# source.net
KiCad netlist of a schematic drawn in Altium Designer
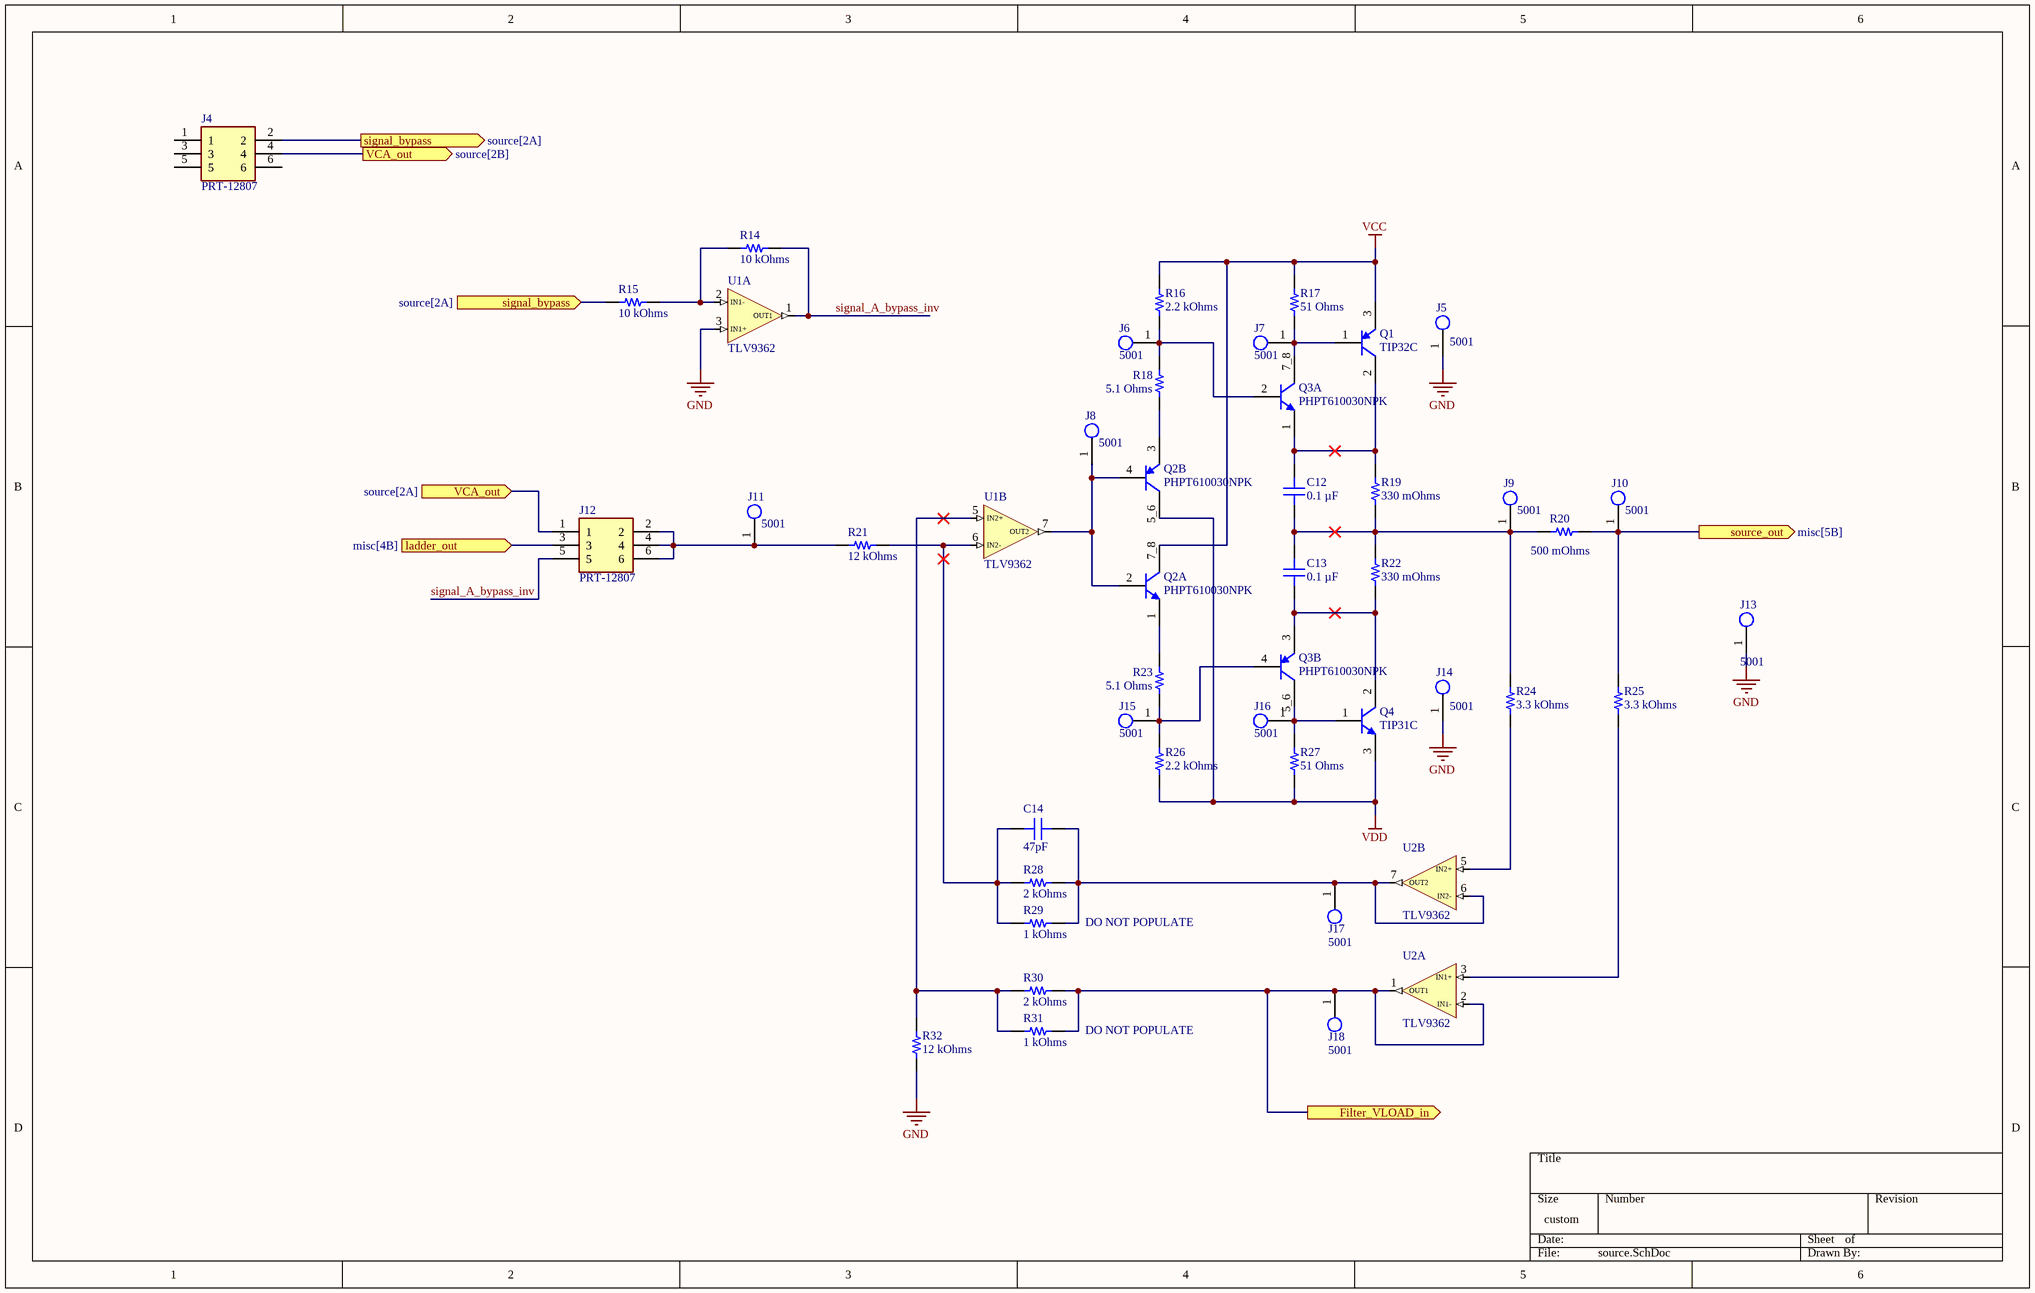
[diagram p0: source.SchDoc]

(export (version "E")
  (design (tool "Eeschema 10.0.6"))
  (components
    (comp (ref "C12")
      (value "0.1 µF")
      (footprint "CAP 1206_3216 - 0.8MM")
      (description "CAP CER 0.1UF 50V X7R 1206")
      (fields
        (field (name "PART NUMBER") "885012208087")
        (field (name "CAPACITANCE") "0.1 µF")
        (field (name "MANUFACTURER") "Würth Elektronik")
      )
      (libsource (lib "Celestial Altium Library - altium_library") (part "Capacitor"))
    )
    (comp (ref "C13")
      (value "0.1 µF")
      (footprint "CAP 1206_3216 - 0.8MM")
      (description "CAP CER 0.1UF 50V X7R 1206")
      (fields
        (field (name "PART NUMBER") "885012208087")
        (field (name "CAPACITANCE") "0.1 µF")
        (field (name "MANUFACTURER") "Würth Elektronik")
      )
      (libsource (lib "Celestial Altium Library - altium_library") (part "Capacitor"))
    )
    (comp (ref "C14")
      (value "47pF")
      (footprint "CAP 1206_3216 - 1.8MM")
      (description "CAP CER 47PF 1KV C0G/NP0 1206")
      (fields
        (field (name "PART NUMBER") "1206AA470KAT1A")
        (field (name "CAPACITANCE") "47pF")
        (field (name "MANUFACTURER") "AVX Corporation")
      )
      (libsource (lib "Celestial Altium Library - altium_library") (part "Capacitor"))
    )
    (comp (ref "J4")
      (value "PRT-12807")
      (footprint "HDRV6W82P254_2X3_762X500X884P")
      (description "Connector")
      (fields (field (name "MOUSER PART NUMBER") "474-PRT-12807"))
      (libsource (lib "za_koncar") (part "PRT-12807"))
    )
    (comp (ref "J5")
      (value "5001")
      (footprint "FP-5001-MFG")
      (description "PC TEST POINT MINIATURE BLACK")
      (libsource (lib "za_koncar") (part "CMP-2000-05181-2"))
    )
    (comp (ref "J6")
      (value "5001")
      (footprint "FP-5001-MFG")
      (description "PC TEST POINT MINIATURE BLACK")
      (libsource (lib "za_koncar") (part "CMP-2000-05181-2"))
    )
    (comp (ref "J7")
      (value "5001")
      (footprint "FP-5001-MFG")
      (description "PC TEST POINT MINIATURE BLACK")
      (libsource (lib "za_koncar") (part "CMP-2000-05181-2"))
    )
    (comp (ref "J8")
      (value "5001")
      (footprint "FP-5001-MFG")
      (description "PC TEST POINT MINIATURE BLACK")
      (libsource (lib "za_koncar") (part "CMP-2000-05181-2"))
    )
    (comp (ref "J9")
      (value "5001")
      (footprint "FP-5001-MFG")
      (description "PC TEST POINT MINIATURE BLACK")
      (libsource (lib "za_koncar") (part "CMP-2000-05181-2"))
    )
    (comp (ref "J10")
      (value "5001")
      (footprint "FP-5001-MFG")
      (description "PC TEST POINT MINIATURE BLACK")
      (libsource (lib "za_koncar") (part "CMP-2000-05181-2"))
    )
    (comp (ref "J11")
      (value "5001")
      (footprint "FP-5001-MFG")
      (description "PC TEST POINT MINIATURE BLACK")
      (libsource (lib "za_koncar") (part "CMP-2000-05181-2"))
    )
    (comp (ref "J12")
      (value "PRT-12807")
      (footprint "HDRV6W82P254_2X3_762X500X884P")
      (description "Connector")
      (fields (field (name "MOUSER PART NUMBER") "474-PRT-12807"))
      (libsource (lib "za_koncar") (part "PRT-12807"))
    )
    (comp (ref "J13")
      (value "5001")
      (footprint "FP-5001-MFG")
      (description "PC TEST POINT MINIATURE BLACK")
      (libsource (lib "za_koncar") (part "CMP-2000-05181-2"))
    )
    (comp (ref "J14")
      (value "5001")
      (footprint "FP-5001-MFG")
      (description "PC TEST POINT MINIATURE BLACK")
      (libsource (lib "za_koncar") (part "CMP-2000-05181-2"))
    )
    (comp (ref "J15")
      (value "5001")
      (footprint "FP-5001-MFG")
      (description "PC TEST POINT MINIATURE BLACK")
      (libsource (lib "za_koncar") (part "CMP-2000-05181-2"))
    )
    (comp (ref "J16")
      (value "5001")
      (footprint "FP-5001-MFG")
      (description "PC TEST POINT MINIATURE BLACK")
      (libsource (lib "za_koncar") (part "CMP-2000-05181-2"))
    )
    (comp (ref "J17")
      (value "5001")
      (footprint "FP-5001-MFG")
      (description "PC TEST POINT MINIATURE BLACK")
      (libsource (lib "za_koncar") (part "CMP-2000-05181-2"))
    )
    (comp (ref "J18")
      (value "5001")
      (footprint "FP-5001-MFG")
      (description "PC TEST POINT MINIATURE BLACK")
      (libsource (lib "za_koncar") (part "CMP-2000-05181-2"))
    )
    (comp (ref "Q1")
      (value "TIP32C")
      (footprint "ONSC-TO-220-3-221A-09")
      (description "Complementary Silicon Plastic Power Transistor, 3-Pin TO-220, Tube")
      (fields (field (name "MANUFACTURER") "On Semiconductor"))
      (libsource (lib "ON Semi General Purpose Transistors") (part "TIP32C"))
    )
    (comp (ref "Q2")
      (value "PHPT610030NPK")
      (footprint "TRANS_BUK9K18-40E,115")
      (libsource (lib "za_koncar") (part "PHPT610030NPK"))
    )
    (comp (ref "Q3")
      (value "PHPT610030NPK")
      (footprint "TRANS_BUK9K18-40E,115")
      (libsource (lib "za_koncar") (part "PHPT610030NPK"))
    )
    (comp (ref "Q4")
      (value "TIP31C")
      (footprint "ONSC-TO-220-3-221A-09")
      (description "Complementary Silicon Plastic Power Transistor, 3-Pin TO-220, Tube")
      (fields (field (name "MANUFACTURER") "On Semiconductor"))
      (libsource (lib "ON Semi General Purpose Transistors") (part "TIP31C"))
    )
    (comp (ref "R14")
      (value "10 kOhms")
      (footprint "YAGEO RES 1206_3216")
      (description "RES SMD 10K OHM 1% 1/4W 1206")
      (fields (field (name "PART NUMBER") "RT1206FRE0710KL") (field (name "MANUFACTURER") "Yageo"))
      (libsource (lib "Celestial Altium Library - altium_library") (part "Resistor"))
    )
    (comp (ref "R15")
      (value "10 kOhms")
      (footprint "YAGEO RES 1206_3216")
      (description "RES SMD 10K OHM 1% 1/4W 1206")
      (fields (field (name "PART NUMBER") "RT1206FRE0710KL") (field (name "MANUFACTURER") "Yageo"))
      (libsource (lib "Celestial Altium Library - altium_library") (part "Resistor"))
    )
    (comp (ref "R16")
      (value "2.2 kOhms")
      (footprint "RES 1206_3216")
      (description "RES SMD 2.2K OHM 5% 1/4W 1206")
      (fields
        (field (name "PART NUMBER") "ERJ-8GEYJ222V")
        (field (name "MANUFACTURER") "Panasonic Electronic Components")
      )
      (libsource (lib "Celestial Altium Library - altium_library") (part "Resistor"))
    )
    (comp (ref "R17")
      (value "51 Ohms")
      (footprint "RES 1206_3216")
      (description "RES SMD 51 OHM 5% 1/4W 1206")
      (fields
        (field (name "PART NUMBER") "ERJ-8GEYJ510V")
        (field (name "MANUFACTURER") "Panasonic Electronic Components")
      )
      (libsource (lib "Celestial Altium Library - altium_library") (part "Resistor"))
    )
    (comp (ref "R18")
      (value "5.1 Ohms")
      (footprint "RES 1206_3216")
      (description "RES SMD 5.1 OHM 5% 1/4W 1206")
      (fields
        (field (name "PART NUMBER") "ERJ-8GEYJ5R1V")
        (field (name "MANUFACTURER") "Panasonic Electronic Components")
      )
      (libsource (lib "Celestial Altium Library - altium_library") (part "Resistor"))
    )
    (comp (ref "R19")
      (value "330 mOhms")
      (footprint "STACKPOLE CSR2512")
      (description "RES 0.33 OHM 1% 2W 2512")
      (fields
        (field (name "PART NUMBER") "CSRN2512FKR330")
        (field (name "MANUFACTURER") "Stackpole Electronics Inc")
      )
      (libsource (lib "Celestial Altium Library - altium_library") (part "Resistor"))
    )
    (comp (ref "R20")
      (value "500 mOhms")
      (footprint "STACKPOLE CSR2512")
      (description "RES 0.5 OHM 1% 2W 2512")
      (fields
        (field (name "PART NUMBER") "CSRN2512FKR500")
        (field (name "MANUFACTURER") "Stackpole Electronics Inc")
      )
      (libsource (lib "Celestial Altium Library - altium_library") (part "Resistor"))
    )
    (comp (ref "R21")
      (value "12 kOhms")
      (footprint "RES 1206_3216")
      (description "RES SMD 12K OHM 0.1% 1/4W 1206")
      (fields
        (field (name "PART NUMBER") "ERA-8AEB123V")
        (field (name "MANUFACTURER") "Panasonic Electronic Components")
      )
      (libsource (lib "Celestial Altium Library - altium_library") (part "Resistor"))
    )
    (comp (ref "R22")
      (value "330 mOhms")
      (footprint "STACKPOLE CSR2512")
      (description "RES 0.33 OHM 1% 2W 2512")
      (fields
        (field (name "PART NUMBER") "CSRN2512FKR330")
        (field (name "MANUFACTURER") "Stackpole Electronics Inc")
      )
      (libsource (lib "Celestial Altium Library - altium_library") (part "Resistor"))
    )
    (comp (ref "R23")
      (value "5.1 Ohms")
      (footprint "RES 1206_3216")
      (description "RES SMD 5.1 OHM 5% 1/4W 1206")
      (fields
        (field (name "PART NUMBER") "ERJ-8GEYJ5R1V")
        (field (name "MANUFACTURER") "Panasonic Electronic Components")
      )
      (libsource (lib "Celestial Altium Library - altium_library") (part "Resistor"))
    )
    (comp (ref "R24")
      (value "3.3 kOhms")
      (footprint "YAGEO RES 1206_3216")
      (description "RES SMD 3.3K OHM 1% 1/4W 1206")
      (fields (field (name "PART NUMBER") "RT1206FRE073K3L") (field (name "MANUFACTURER") "Yageo"))
      (libsource (lib "Celestial Altium Library - altium_library") (part "Resistor"))
    )
    (comp (ref "R25")
      (value "3.3 kOhms")
      (footprint "YAGEO RES 1206_3216")
      (description "RES SMD 3.3K OHM 1% 1/4W 1206")
      (fields (field (name "PART NUMBER") "RT1206FRE073K3L") (field (name "MANUFACTURER") "Yageo"))
      (libsource (lib "Celestial Altium Library - altium_library") (part "Resistor"))
    )
    (comp (ref "R26")
      (value "2.2 kOhms")
      (footprint "RES 1206_3216")
      (description "RES SMD 2.2K OHM 5% 1/4W 1206")
      (fields
        (field (name "PART NUMBER") "ERJ-8GEYJ222V")
        (field (name "MANUFACTURER") "Panasonic Electronic Components")
      )
      (libsource (lib "Celestial Altium Library - altium_library") (part "Resistor"))
    )
    (comp (ref "R27")
      (value "51 Ohms")
      (footprint "RES 1206_3216")
      (description "RES SMD 51 OHM 5% 1/4W 1206")
      (fields
        (field (name "PART NUMBER") "ERJ-8GEYJ510V")
        (field (name "MANUFACTURER") "Panasonic Electronic Components")
      )
      (libsource (lib "Celestial Altium Library - altium_library") (part "Resistor"))
    )
    (comp (ref "R28")
      (value "2 kOhms")
      (footprint "RES 1206_3216")
      (description "RES SMD 2K OHM 0.1% 1/4W 1206")
      (fields
        (field (name "PART NUMBER") "ERA-8AEB202V")
        (field (name "MANUFACTURER") "Panasonic Electronic Components")
      )
      (libsource (lib "Celestial Altium Library - altium_library") (part "Resistor"))
    )
    (comp (ref "R29")
      (value "1 kOhms")
      (footprint "RES 1206_3216")
      (description "RES SMD 1K OHM 0.1% 1/4W 1206")
      (fields
        (field (name "PART NUMBER") "ERA-8AEB102V")
        (field (name "MANUFACTURER") "Panasonic Electronic Components")
      )
      (libsource (lib "Celestial Altium Library - altium_library") (part "Resistor"))
    )
    (comp (ref "R30")
      (value "2 kOhms")
      (footprint "RES 1206_3216")
      (description "RES SMD 2K OHM 0.1% 1/4W 1206")
      (fields
        (field (name "PART NUMBER") "ERA-8AEB202V")
        (field (name "MANUFACTURER") "Panasonic Electronic Components")
      )
      (libsource (lib "Celestial Altium Library - altium_library") (part "Resistor"))
    )
    (comp (ref "R31")
      (value "1 kOhms")
      (footprint "RES 1206_3216")
      (description "RES SMD 1K OHM 0.1% 1/4W 1206")
      (fields
        (field (name "PART NUMBER") "ERA-8AEB102V")
        (field (name "MANUFACTURER") "Panasonic Electronic Components")
      )
      (libsource (lib "Celestial Altium Library - altium_library") (part "Resistor"))
    )
    (comp (ref "R32")
      (value "12 kOhms")
      (footprint "RES 1206_3216")
      (description "RES SMD 12K OHM 0.1% 1/4W 1206")
      (fields
        (field (name "PART NUMBER") "ERA-8AEB123V")
        (field (name "MANUFACTURER") "Panasonic Electronic Components")
      )
      (libsource (lib "Celestial Altium Library - altium_library") (part "Resistor"))
    )
    (comp (ref "U1")
      (value "TLV9362")
      (footprint "SOIC8-127P600X175-8N")
      (description "TLV936x 10-MHz, 40-V, RRO, Operational Amplifie")
      (libsource (lib "za_koncar") (part "TLV9362"))
    )
    (comp (ref "U2")
      (value "TLV9362")
      (footprint "SOIC8-127P600X175-8N")
      (description "TLV936x 10-MHz, 40-V, RRO, Operational Amplifie")
      (libsource (lib "za_koncar") (part "TLV9362"))
    )
  )
  (nets
    (net (code "1") (name "/Filter_VLOAD_in") (class "Default")
      (node (ref "J18") (pin "1") (pinfunction "1_1") (pintype "passive"))
      (node (ref "R30") (pin "2") (pinfunction "2_2") (pintype "passive"))
      (node (ref "R31") (pin "2") (pinfunction "2_2") (pintype "passive"))
      (node (ref "U2") (pin "1") (pinfunction "OUT1_1") (pintype "output"))
      (node (ref "U2") (pin "2") (pinfunction "IN1-_2") (pintype "input"))
    )
    (net (code "2") (name "/VCA_out") (class "Default")
      (node (ref "J12") (pin "1") (pinfunction "1_1") (pintype "passive"))
      (node (ref "J4") (pin "4") (pinfunction "4_4") (pintype "passive"))
    )
    (net (code "3") (name "/ladder_out") (class "Default")
      (node (ref "J12") (pin "3") (pinfunction "3_3") (pintype "passive"))
    )
    (net (code "4") (name "/signal_A_bypass_inv") (class "Default")
      (node (ref "J12") (pin "5") (pinfunction "5_5") (pintype "passive"))
      (node (ref "R14") (pin "2") (pinfunction "2_2") (pintype "passive"))
      (node (ref "U1") (pin "1") (pinfunction "OUT1_1") (pintype "output"))
    )
    (net (code "5") (name "/signal_bypass") (class "Default")
      (node (ref "J4") (pin "2") (pinfunction "2_2") (pintype "passive"))
      (node (ref "R15") (pin "2") (pinfunction "2_2") (pintype "passive"))
    )
    (net (code "6") (name "/source_out") (class "Default")
      (node (ref "J10") (pin "1") (pinfunction "1_1") (pintype "passive"))
      (node (ref "R20") (pin "1") (pinfunction "1_1") (pintype "passive"))
      (node (ref "R25") (pin "1") (pinfunction "1_1") (pintype "passive"))
    )
    (net (code "7") (name "GND") (class "Default")
      (node (ref "J13") (pin "1") (pinfunction "1_1") (pintype "passive"))
      (node (ref "J14") (pin "1") (pinfunction "1_1") (pintype "passive"))
      (node (ref "J5") (pin "1") (pinfunction "1_1") (pintype "passive"))
      (node (ref "R32") (pin "1") (pinfunction "1_1") (pintype "passive"))
      (node (ref "U1") (pin "3") (pinfunction "IN1+_3") (pintype "input"))
    )
    (net (code "8") (name "Net-(C12-Pad1)") (class "Default")
      (node (ref "C12") (pin "1") (pinfunction "1_1") (pintype "passive"))
      (node (ref "C13") (pin "2") (pinfunction "2_2") (pintype "passive"))
      (node (ref "J9") (pin "1") (pinfunction "1_1") (pintype "passive"))
      (node (ref "R19") (pin "1") (pinfunction "1_1") (pintype "passive"))
      (node (ref "R20") (pin "2") (pinfunction "2_2") (pintype "passive"))
      (node (ref "R22") (pin "2") (pinfunction "2_2") (pintype "passive"))
      (node (ref "R24") (pin "1") (pinfunction "1_1") (pintype "passive"))
    )
    (net (code "9") (name "Net-(J11-Pad1)") (class "Default")
      (node (ref "J11") (pin "1") (pinfunction "1_1") (pintype "passive"))
      (node (ref "J12") (pin "2") (pinfunction "2_2") (pintype "passive"))
      (node (ref "J12") (pin "4") (pinfunction "4_4") (pintype "passive"))
      (node (ref "J12") (pin "6") (pinfunction "6_6") (pintype "passive"))
      (node (ref "R21") (pin "2") (pinfunction "2_2") (pintype "passive"))
    )
    (net (code "10") (name "Net-(Q1-B)") (class "Default")
      (node (ref "J7") (pin "1") (pinfunction "1_1") (pintype "passive"))
      (node (ref "Q1") (pin "1") (pinfunction "B_1") (pintype "passive"))
      (node (ref "Q3") (pin "7_8") (pinfunction "C1_7_8") (pintype "passive"))
      (node (ref "R17") (pin "1") (pinfunction "1_1") (pintype "passive"))
    )
    (net (code "11") (name "Net-(Q1-C)") (class "Default")
      (node (ref "C12") (pin "2") (pinfunction "2_2") (pintype "passive"))
      (node (ref "Q1") (pin "2") (pinfunction "C_2") (pintype "passive"))
      (node (ref "Q3") (pin "1") (pinfunction "E1_1") (pintype "passive"))
      (node (ref "R19") (pin "2") (pinfunction "2_2") (pintype "passive"))
    )
    (net (code "12") (name "Net-(Q2A-B1)") (class "Default")
      (node (ref "J8") (pin "1") (pinfunction "1_1") (pintype "passive"))
      (node (ref "Q2") (pin "2") (pinfunction "B1_2") (pintype "passive"))
      (node (ref "Q2") (pin "4") (pinfunction "B2_4") (pintype "passive"))
      (node (ref "U1") (pin "7") (pinfunction "OUT2_7") (pintype "output"))
    )
    (net (code "13") (name "Net-(Q2A-E1)") (class "Default")
      (node (ref "Q2") (pin "1") (pinfunction "E1_1") (pintype "passive"))
      (node (ref "R23") (pin "2") (pinfunction "2_2") (pintype "passive"))
    )
    (net (code "14") (name "Net-(Q2B-E2)") (class "Default")
      (node (ref "Q2") (pin "3") (pinfunction "E2_3") (pintype "passive"))
      (node (ref "R18") (pin "1") (pinfunction "1_1") (pintype "passive"))
    )
    (net (code "15") (name "Net-(Q3A-B1)") (class "Default")
      (node (ref "J6") (pin "1") (pinfunction "1_1") (pintype "passive"))
      (node (ref "Q3") (pin "2") (pinfunction "B1_2") (pintype "passive"))
      (node (ref "R16") (pin "1") (pinfunction "1_1") (pintype "passive"))
      (node (ref "R18") (pin "2") (pinfunction "2_2") (pintype "passive"))
    )
    (net (code "16") (name "Net-(Q3B-B2)") (class "Default")
      (node (ref "J15") (pin "1") (pinfunction "1_1") (pintype "passive"))
      (node (ref "Q3") (pin "4") (pinfunction "B2_4") (pintype "passive"))
      (node (ref "R23") (pin "1") (pinfunction "1_1") (pintype "passive"))
      (node (ref "R26") (pin "2") (pinfunction "2_2") (pintype "passive"))
    )
    (net (code "17") (name "Net-(Q3B-C2)") (class "Default")
      (node (ref "J16") (pin "1") (pinfunction "1_1") (pintype "passive"))
      (node (ref "Q3") (pin "5_6") (pinfunction "C2_5_6") (pintype "passive"))
      (node (ref "Q4") (pin "1") (pinfunction "B_1") (pintype "passive"))
      (node (ref "R27") (pin "2") (pinfunction "2_2") (pintype "passive"))
    )
    (net (code "18") (name "Net-(Q3B-E2)") (class "Default")
      (node (ref "C13") (pin "1") (pinfunction "1_1") (pintype "passive"))
      (node (ref "Q3") (pin "3") (pinfunction "E2_3") (pintype "passive"))
      (node (ref "Q4") (pin "2") (pinfunction "C_2") (pintype "passive"))
      (node (ref "R22") (pin "1") (pinfunction "1_1") (pintype "passive"))
    )
    (net (code "19") (name "Net-(U1A-IN1-)") (class "Default")
      (node (ref "R14") (pin "1") (pinfunction "1_1") (pintype "passive"))
      (node (ref "R15") (pin "1") (pinfunction "1_1") (pintype "passive"))
      (node (ref "U1") (pin "2") (pinfunction "IN1-_2") (pintype "input"))
    )
    (net (code "20") (name "Net-(U1B-IN2+)") (class "Default")
      (node (ref "R30") (pin "1") (pinfunction "1_1") (pintype "passive"))
      (node (ref "R31") (pin "1") (pinfunction "1_1") (pintype "passive"))
      (node (ref "R32") (pin "2") (pinfunction "2_2") (pintype "passive"))
      (node (ref "U1") (pin "5") (pinfunction "IN2+_5") (pintype "input"))
    )
    (net (code "21") (name "Net-(U1B-IN2-)") (class "Default")
      (node (ref "C14") (pin "1") (pinfunction "1_1") (pintype "passive"))
      (node (ref "R21") (pin "1") (pinfunction "1_1") (pintype "passive"))
      (node (ref "R28") (pin "1") (pinfunction "1_1") (pintype "passive"))
      (node (ref "R29") (pin "1") (pinfunction "1_1") (pintype "passive"))
      (node (ref "U1") (pin "6") (pinfunction "IN2-_6") (pintype "input"))
    )
    (net (code "22") (name "Net-(U2A-IN1+)") (class "Default")
      (node (ref "R25") (pin "2") (pinfunction "2_2") (pintype "passive"))
      (node (ref "U2") (pin "3") (pinfunction "IN1+_3") (pintype "input"))
    )
    (net (code "23") (name "Net-(U2B-IN2+)") (class "Default")
      (node (ref "R24") (pin "2") (pinfunction "2_2") (pintype "passive"))
      (node (ref "U2") (pin "5") (pinfunction "IN2+_5") (pintype "input"))
    )
    (net (code "24") (name "Net-(U2B-IN2-)") (class "Default")
      (node (ref "C14") (pin "2") (pinfunction "2_2") (pintype "passive"))
      (node (ref "J17") (pin "1") (pinfunction "1_1") (pintype "passive"))
      (node (ref "R28") (pin "2") (pinfunction "2_2") (pintype "passive"))
      (node (ref "R29") (pin "2") (pinfunction "2_2") (pintype "passive"))
      (node (ref "U2") (pin "6") (pinfunction "IN2-_6") (pintype "input"))
      (node (ref "U2") (pin "7") (pinfunction "OUT2_7") (pintype "output"))
    )
    (net (code "25") (name "VCC") (class "Default")
      (node (ref "Q1") (pin "3") (pinfunction "E_3") (pintype "passive"))
      (node (ref "Q2") (pin "7_8") (pinfunction "C1_7_8") (pintype "passive"))
      (node (ref "R16") (pin "2") (pinfunction "2_2") (pintype "passive"))
      (node (ref "R17") (pin "2") (pinfunction "2_2") (pintype "passive"))
    )
    (net (code "26") (name "VDD") (class "Default")
      (node (ref "Q2") (pin "5_6") (pinfunction "C2_5_6") (pintype "passive"))
      (node (ref "Q4") (pin "3") (pinfunction "E_3") (pintype "passive"))
      (node (ref "R26") (pin "1") (pinfunction "1_1") (pintype "passive"))
      (node (ref "R27") (pin "1") (pinfunction "1_1") (pintype "passive"))
    )
    (net (code "27") (name "unconnected-(J4-Pad1)") (class "Default")
      (node (ref "J4") (pin "1") (pinfunction "1_1") (pintype "passive"))
    )
    (net (code "28") (name "unconnected-(J4-Pad3)") (class "Default")
      (node (ref "J4") (pin "3") (pinfunction "3_3") (pintype "passive"))
    )
    (net (code "29") (name "unconnected-(J4-Pad5)") (class "Default")
      (node (ref "J4") (pin "5") (pinfunction "5_5") (pintype "passive"))
    )
    (net (code "30") (name "unconnected-(J4-Pad6)") (class "Default")
      (node (ref "J4") (pin "6") (pinfunction "6_6") (pintype "passive"))
    )
  )
)
